# chanel.net
KiCad netlist of a schematic drawn in Altium Designer
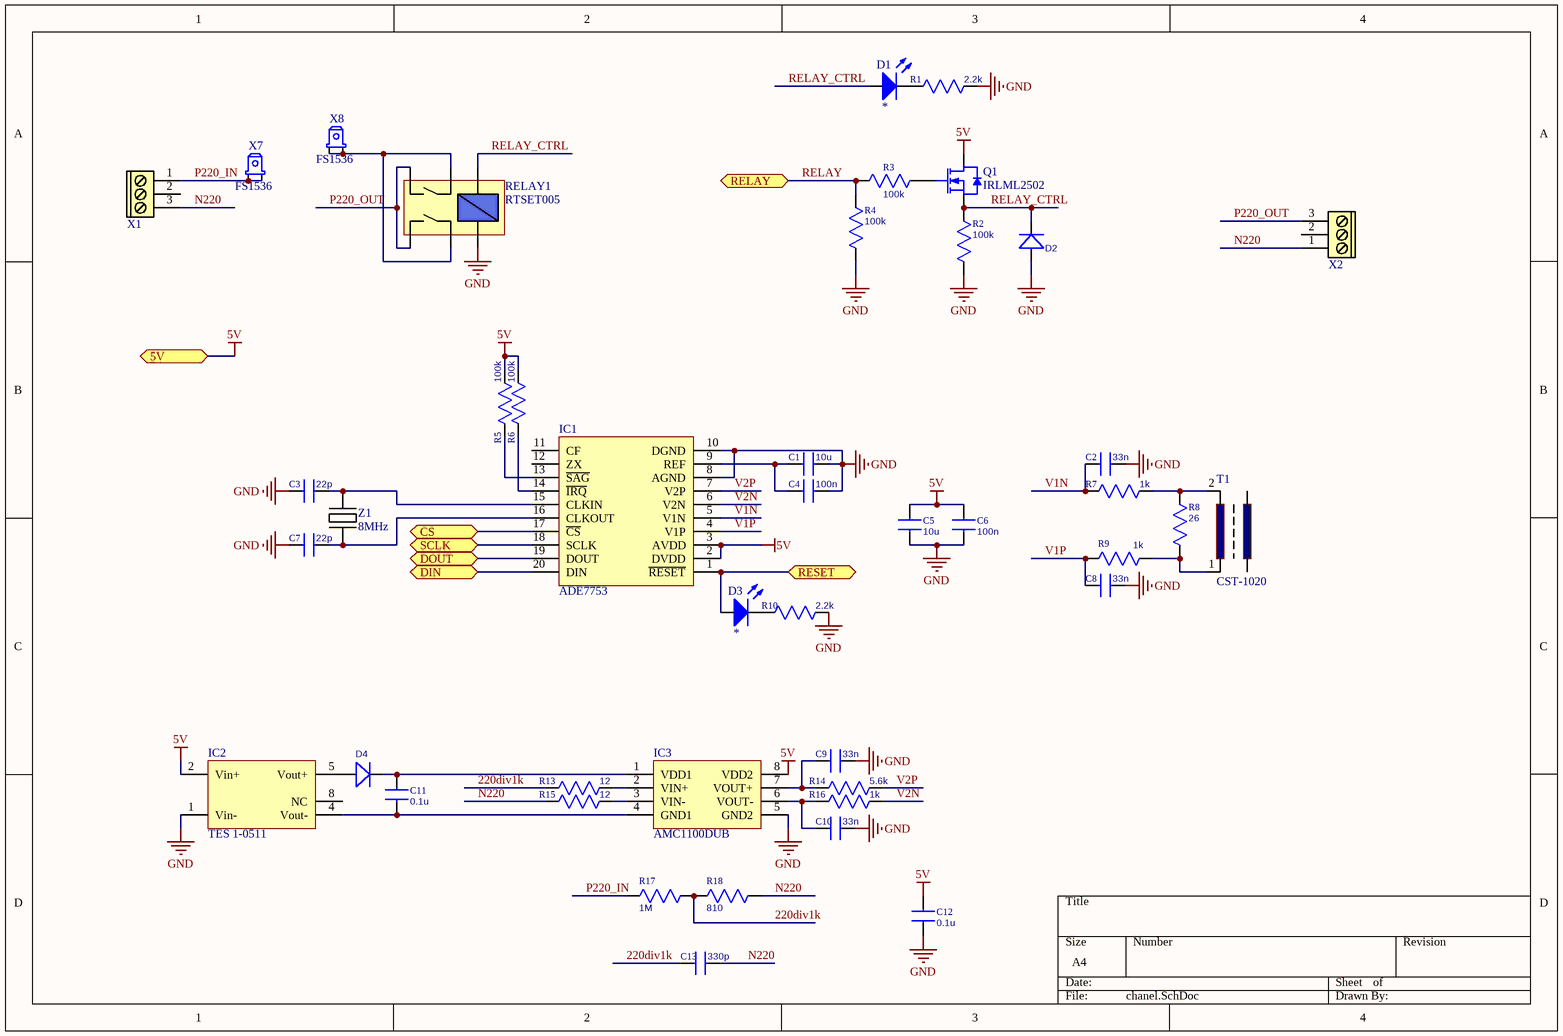
[diagram p0: chanel.SchDoc]

(export (version "E")
  (design (tool "Eeschema 10.0.6"))
  (components
    (comp (ref "C1")
      (value "10u")
      (footprint "C_0805")
      (description "Capacitor")
      (libsource (lib "AX_Altium_v2.3") (part "C0805"))
    )
    (comp (ref "C2")
      (value "33n")
      (footprint "C_0603")
      (description "Capacitor")
      (libsource (lib "AX_Altium_v2.3") (part "C0603"))
    )
    (comp (ref "C3")
      (value "22p")
      (footprint "C_0603")
      (description "Capacitor")
      (libsource (lib "AX_Altium_v2.3") (part "C0603"))
    )
    (comp (ref "C4")
      (value "100n")
      (footprint "C_0603")
      (description "Capacitor")
      (libsource (lib "AX_Altium_v2.3") (part "C0603"))
    )
    (comp (ref "C5")
      (value "10u")
      (footprint "C_0805")
      (description "Capacitor")
      (libsource (lib "AX_Altium_v2.3") (part "C0805"))
    )
    (comp (ref "C6")
      (value "100n")
      (footprint "C_0603")
      (description "Capacitor")
      (libsource (lib "AX_Altium_v2.3") (part "C0603"))
    )
    (comp (ref "C7")
      (value "22p")
      (footprint "C_0603")
      (description "Capacitor")
      (libsource (lib "AX_Altium_v2.3") (part "C0603"))
    )
    (comp (ref "C8")
      (value "33n")
      (footprint "C_0603")
      (description "Capacitor")
      (libsource (lib "AX_Altium_v2.3") (part "C0603"))
    )
    (comp (ref "C9")
      (value "33n")
      (footprint "C_0603")
      (description "Capacitor")
      (libsource (lib "AX_Altium_v2.3") (part "C0603"))
    )
    (comp (ref "C10")
      (value "33n")
      (footprint "C_0603")
      (description "Capacitor")
      (libsource (lib "AX_Altium_v2.3") (part "C0603"))
    )
    (comp (ref "C11")
      (value "0.1u")
      (footprint "C_0603")
      (description "Capacitor")
      (libsource (lib "AX_Altium_v2.3") (part "C0603"))
    )
    (comp (ref "C12")
      (value "0.1u")
      (footprint "C_0603")
      (description "Capacitor")
      (libsource (lib "AX_Altium_v2.3") (part "C0603"))
    )
    (comp (ref "C13")
      (value "330p")
      (footprint "C_0603")
      (description "Capacitor")
      (libsource (lib "AX_Altium_v2.3") (part "C0603"))
    )
    (comp (ref "D1")
      (value "*")
      (footprint "LED_5mm")
      (description "Typical INFRARED GaAs LED")
      (libsource (lib "AX_Altium_v2.3") (part "LED_5mm"))
    )
    (comp (ref "D2")
      (value "D_DO-214AC")
      (footprint "DO-214AC")
      (description "Diode")
      (libsource (lib "AX_Altium_v2.3") (part "D_DO-214AC"))
    )
    (comp (ref "D3")
      (value "*")
      (footprint "LED_5mm")
      (description "Typical INFRARED GaAs LED")
      (libsource (lib "AX_Altium_v2.3") (part "LED_5mm"))
    )
    (comp (ref "D4")
      (value "D_DO-214AC")
      (footprint "DO-214AC")
      (description "Diode")
      (libsource (lib "AX_Altium_v2.3") (part "D_DO-214AC"))
    )
    (comp (ref "IC1")
      (value "ADE7753")
      (footprint "SOP-20")
      (description "Data Acquisition ADC/DAC")
      (libsource (lib "SmartOutletIntegratedLibrary") (part "ADE7753ARSZ"))
    )
    (comp (ref "IC2")
      (value "TES 1-0511")
      (footprint "TES 1-0511")
      (description "Isolated DC/DC Converter")
      (libsource (lib "SmartOutletIntegratedLibrary") (part "TES 1-0511"))
    )
    (comp (ref "IC3")
      (value "AMC1100DUB")
      (footprint "SOP254-8N")
      (description "Isolation Amplifier 4.25kV PEAK Iso Amp")
      (libsource (lib "SmartOutletIntegratedLibrary") (part "AMC1100DUB"))
    )
    (comp (ref "Q1")
      (value "IRLML2502")
      (footprint "SOT23")
      (description "N-Channel Enhancement Mode MOSFET")
      (fields (field (name "PUBLISHER") "Altium Limited"))
      (libsource (lib "AX_Altium_v2.3") (part "N-ch_SOT23"))
    )
    (comp (ref "R1")
      (value "2.2k")
      (footprint "R_0603")
      (description "Resistor")
      (libsource (lib "AX_Altium_v2.3") (part "R0603"))
    )
    (comp (ref "R2")
      (value "100k")
      (footprint "R_0603")
      (description "Resistor")
      (libsource (lib "AX_Altium_v2.3") (part "R0603"))
    )
    (comp (ref "R3")
      (value "100k")
      (footprint "R_0603")
      (description "Resistor")
      (libsource (lib "AX_Altium_v2.3") (part "R0603"))
    )
    (comp (ref "R4")
      (value "100k")
      (footprint "R_0603")
      (description "Resistor")
      (libsource (lib "AX_Altium_v2.3") (part "R0603"))
    )
    (comp (ref "R5")
      (value "100k")
      (footprint "R_0603")
      (description "Resistor")
      (libsource (lib "AX_Altium_v2.3") (part "R0603"))
    )
    (comp (ref "R6")
      (value "100k")
      (footprint "R_0603")
      (description "Resistor")
      (libsource (lib "AX_Altium_v2.3") (part "R0603"))
    )
    (comp (ref "R7")
      (value "1k")
      (footprint "R_0603")
      (description "Resistor")
      (libsource (lib "AX_Altium_v2.3") (part "R0603"))
    )
    (comp (ref "R8")
      (value "26")
      (footprint "R_0805")
      (description "Resistor")
      (libsource (lib "AX_Altium_v2.3") (part "R0805"))
    )
    (comp (ref "R9")
      (value "1k")
      (footprint "R_0603")
      (description "Resistor")
      (libsource (lib "AX_Altium_v2.3") (part "R0603"))
    )
    (comp (ref "R10")
      (value "2.2k")
      (footprint "R_0603")
      (description "Resistor")
      (libsource (lib "AX_Altium_v2.3") (part "R0603"))
    )
    (comp (ref "R13")
      (value "12")
      (footprint "R_0603")
      (description "Resistor")
      (libsource (lib "AX_Altium_v2.3") (part "R0603"))
    )
    (comp (ref "R14")
      (value "5.6k")
      (footprint "R_0603")
      (description "Resistor")
      (libsource (lib "AX_Altium_v2.3") (part "R0603"))
    )
    (comp (ref "R15")
      (value "12")
      (footprint "R_0603")
      (description "Resistor")
      (libsource (lib "AX_Altium_v2.3") (part "R0603"))
    )
    (comp (ref "R16")
      (value "1k")
      (footprint "R_0603")
      (description "Resistor")
      (libsource (lib "AX_Altium_v2.3") (part "R0603"))
    )
    (comp (ref "R17")
      (value "1M")
      (footprint "R_0805")
      (description "Resistor")
      (libsource (lib "AX_Altium_v2.3") (part "R0805"))
    )
    (comp (ref "R18")
      (value "810")
      (footprint "R_0805")
      (description "Resistor")
      (libsource (lib "AX_Altium_v2.3") (part "R0805"))
    )
    (comp (ref "RELAY1")
      (value "RTSET005")
      (footprint "RTSET005")
      (description "General Purpose Relay")
      (libsource (lib "SmartOutletIntegratedLibrary") (part "1-1415898-8"))
    )
    (comp (ref "T1")
      (value "CST-1020")
      (footprint "CST-1020")
      (description "Current Transformer")
      (libsource (lib "SmartOutletIntegratedLibrary") (part "CST-1020"))
    )
    (comp (ref "X1")
      (value "DG-300-3")
      (footprint "DG-300-5MM-3")
      (libsource (lib "Light_Music_Integrated_Library") (part "DG-300-3"))
    )
    (comp (ref "X2") (value "DG-300-3") (footprint "DG-300-5MM-3") (libsource (lib "") (part "DG-300-3_1")))
    (comp (ref "X7")
      (value "FS1536")
      (footprint "FS1536")
      (description "PCB Soldering tips")
      (libsource (lib "SmartOutletIntegratedLibrary") (part "FS1536"))
    )
    (comp (ref "X8")
      (value "FS1536")
      (footprint "FS1536")
      (description "PCB Soldering tips")
      (libsource (lib "SmartOutletIntegratedLibrary") (part "FS1536"))
    )
    (comp (ref "Z1")
      (value "8MHz")
      (footprint "HC-49")
      (description "Quartz resonator")
      (libsource (lib "Light_Music_Integrated_Library") (part "XTAL"))
    )
  )
  (nets
    (net (code "1") (name "/220div1k") (class "Default")
      (node (ref "C13") (pin "1") (pintype "passive"))
      (node (ref "R13") (pin "1") (pintype "passive"))
      (node (ref "R17") (pin "2") (pintype "passive"))
      (node (ref "R18") (pin "1") (pintype "passive"))
    )
    (net (code "2") (name "/CS") (class "Default")
      (node (ref "IC1") (pin "17") (pinfunction "~{CS}_17") (pintype "passive"))
    )
    (net (code "3") (name "/DIN") (class "Default")
      (node (ref "IC1") (pin "20") (pinfunction "DIN_20") (pintype "passive"))
    )
    (net (code "4") (name "/DOUT") (class "Default")
      (node (ref "IC1") (pin "19") (pinfunction "DOUT_19") (pintype "passive"))
    )
    (net (code "5") (name "/N220") (class "Default")
      (node (ref "C13") (pin "2") (pintype "passive"))
      (node (ref "R15") (pin "1") (pintype "passive"))
      (node (ref "R18") (pin "2") (pintype "passive"))
      (node (ref "X1") (pin "3") (pinfunction "3_3") (pintype "passive"))
      (node (ref "X2") (pin "1") (pinfunction "1_1") (pintype "passive"))
    )
    (net (code "6") (name "/P220_IN") (class "Default")
      (node (ref "R17") (pin "1") (pintype "passive"))
      (node (ref "X1") (pin "1") (pinfunction "1_1") (pintype "passive"))
      (node (ref "X7") (pin "1") (pinfunction "1_1") (pintype "passive"))
    )
    (net (code "7") (name "/P220_OUT") (class "Default")
      (node (ref "RELAY1") (pin "1") (pinfunction "1_1") (pintype "passive"))
      (node (ref "RELAY1") (pin "2") (pinfunction "2_2") (pintype "passive"))
      (node (ref "X2") (pin "3") (pinfunction "3_3") (pintype "passive"))
    )
    (net (code "8") (name "/RELAY") (class "Default")
      (node (ref "R3") (pin "2") (pintype "passive"))
      (node (ref "R4") (pin "1") (pintype "passive"))
    )
    (net (code "9") (name "/RELAY_CTRL") (class "Default")
      (node (ref "D1") (pin "1") (pinfunction "A_1") (pintype "passive"))
      (node (ref "D2") (pin "2") (pinfunction "K_2") (pintype "passive"))
      (node (ref "Q1") (pin "2") (pinfunction "S_2") (pintype "passive"))
      (node (ref "R2") (pin "1") (pintype "passive"))
      (node (ref "RELAY1") (pin "5") (pinfunction "5_5") (pintype "passive"))
    )
    (net (code "10") (name "/RESET") (class "Default")
      (node (ref "D3") (pin "1") (pinfunction "A_1") (pintype "passive"))
      (node (ref "IC1") (pin "1") (pinfunction "~{RESET}_1") (pintype "passive"))
    )
    (net (code "11") (name "/SCLK") (class "Default")
      (node (ref "IC1") (pin "18") (pinfunction "SCLK_18") (pintype "passive"))
    )
    (net (code "12") (name "/V1N") (class "Default")
      (node (ref "C2") (pin "1") (pintype "passive"))
      (node (ref "IC1") (pin "5") (pinfunction "V1N_5") (pintype "passive"))
      (node (ref "R7") (pin "1") (pintype "passive"))
    )
    (net (code "13") (name "/V1P") (class "Default")
      (node (ref "C8") (pin "1") (pintype "passive"))
      (node (ref "IC1") (pin "4") (pinfunction "V1P_4") (pintype "passive"))
      (node (ref "R9") (pin "1") (pintype "passive"))
    )
    (net (code "14") (name "/V2N") (class "Default")
      (node (ref "IC1") (pin "6") (pinfunction "V2N_6") (pintype "passive"))
      (node (ref "R16") (pin "2") (pintype "passive"))
    )
    (net (code "15") (name "/V2P") (class "Default")
      (node (ref "IC1") (pin "7") (pinfunction "V2P_7") (pintype "passive"))
      (node (ref "R14") (pin "2") (pintype "passive"))
    )
    (net (code "16") (name "5V") (class "Default")
      (node (ref "C12") (pin "2") (pintype "passive"))
      (node (ref "C5") (pin "2") (pintype "passive"))
      (node (ref "C6") (pin "2") (pintype "passive"))
      (node (ref "IC1") (pin "2") (pinfunction "DVDD_2") (pintype "passive"))
      (node (ref "IC1") (pin "3") (pinfunction "AVDD_3") (pintype "passive"))
      (node (ref "IC2") (pin "2") (pinfunction "Vin+_2") (pintype "passive"))
      (node (ref "IC3") (pin "8") (pinfunction "VDD2_8") (pintype "passive"))
      (node (ref "Q1") (pin "3") (pinfunction "D_3") (pintype "passive"))
      (node (ref "R5") (pin "2") (pintype "passive"))
      (node (ref "R6") (pin "2") (pintype "passive"))
    )
    (net (code "17") (name "GND") (class "Default")
      (node (ref "C1") (pin "2") (pintype "passive"))
      (node (ref "C10") (pin "2") (pintype "passive"))
      (node (ref "C12") (pin "1") (pintype "passive"))
      (node (ref "C2") (pin "2") (pintype "passive"))
      (node (ref "C3") (pin "1") (pintype "passive"))
      (node (ref "C4") (pin "2") (pintype "passive"))
      (node (ref "C5") (pin "1") (pintype "passive"))
      (node (ref "C6") (pin "1") (pintype "passive"))
      (node (ref "C7") (pin "1") (pintype "passive"))
      (node (ref "C8") (pin "2") (pintype "passive"))
      (node (ref "C9") (pin "2") (pintype "passive"))
      (node (ref "D2") (pin "1") (pinfunction "A_1") (pintype "passive"))
      (node (ref "IC1") (pin "10") (pinfunction "DGND_10") (pintype "passive"))
      (node (ref "IC1") (pin "8") (pinfunction "AGND_8") (pintype "passive"))
      (node (ref "IC2") (pin "1") (pinfunction "Vin-_1") (pintype "passive"))
      (node (ref "IC3") (pin "5") (pinfunction "GND2_5") (pintype "passive"))
      (node (ref "R1") (pin "2") (pintype "passive"))
      (node (ref "R10") (pin "2") (pintype "passive"))
      (node (ref "R2") (pin "2") (pintype "passive"))
      (node (ref "R4") (pin "2") (pintype "passive"))
      (node (ref "RELAY1") (pin "6") (pinfunction "6_6") (pintype "passive"))
    )
    (net (code "18") (name "Net-(D1-K)") (class "Default")
      (node (ref "D1") (pin "2") (pinfunction "K_2") (pintype "passive"))
      (node (ref "R1") (pin "1") (pintype "passive"))
    )
    (net (code "19") (name "Net-(D3-K)") (class "Default")
      (node (ref "D3") (pin "2") (pinfunction "K_2") (pintype "passive"))
      (node (ref "R10") (pin "1") (pintype "passive"))
    )
    (net (code "20") (name "Net-(D4-A)") (class "Default")
      (node (ref "D4") (pin "1") (pinfunction "A_1") (pintype "passive"))
      (node (ref "IC2") (pin "5") (pinfunction "Vout+_5") (pintype "passive"))
    )
    (net (code "21") (name "Net-(D4-K)") (class "Default")
      (node (ref "C11") (pin "2") (pintype "passive"))
      (node (ref "D4") (pin "2") (pinfunction "K_2") (pintype "passive"))
      (node (ref "IC3") (pin "1") (pinfunction "VDD1_1") (pintype "passive"))
    )
    (net (code "22") (name "Net-(IC1-CLKIN)") (class "Default")
      (node (ref "C3") (pin "2") (pintype "passive"))
      (node (ref "IC1") (pin "15") (pinfunction "CLKIN_15") (pintype "passive"))
      (node (ref "Z1") (pin "2") (pinfunction "2_2") (pintype "passive"))
    )
    (net (code "23") (name "Net-(IC1-CLKOUT)") (class "Default")
      (node (ref "C7") (pin "2") (pintype "passive"))
      (node (ref "IC1") (pin "16") (pinfunction "CLKOUT_16") (pintype "passive"))
      (node (ref "Z1") (pin "1") (pinfunction "1_1") (pintype "passive"))
    )
    (net (code "24") (name "Net-(IC1-REF)") (class "Default")
      (node (ref "C1") (pin "1") (pintype "passive"))
      (node (ref "C4") (pin "1") (pintype "passive"))
      (node (ref "IC1") (pin "9") (pinfunction "REF_9") (pintype "passive"))
    )
    (net (code "25") (name "Net-(IC1-~{IRQ})") (class "Default")
      (node (ref "IC1") (pin "14") (pinfunction "~{IRQ}_14") (pintype "passive"))
      (node (ref "R6") (pin "1") (pintype "passive"))
    )
    (net (code "26") (name "Net-(IC1-~{SAG})") (class "Default")
      (node (ref "IC1") (pin "13") (pinfunction "~{SAG}_13") (pintype "passive"))
      (node (ref "R5") (pin "1") (pintype "passive"))
    )
    (net (code "27") (name "Net-(IC2-Vout-)") (class "Default")
      (node (ref "C11") (pin "1") (pintype "passive"))
      (node (ref "IC2") (pin "4") (pinfunction "Vout-_4") (pintype "passive"))
      (node (ref "IC3") (pin "4") (pinfunction "GND1_4") (pintype "passive"))
    )
    (net (code "28") (name "Net-(IC3-VIN+)") (class "Default")
      (node (ref "IC3") (pin "2") (pinfunction "VIN+_2") (pintype "passive"))
      (node (ref "R13") (pin "2") (pintype "passive"))
    )
    (net (code "29") (name "Net-(IC3-VIN-)") (class "Default")
      (node (ref "IC3") (pin "3") (pinfunction "VIN-_3") (pintype "passive"))
      (node (ref "R15") (pin "2") (pintype "passive"))
    )
    (net (code "30") (name "Net-(IC3-VOUT+)") (class "Default")
      (node (ref "C9") (pin "1") (pintype "passive"))
      (node (ref "IC3") (pin "7") (pinfunction "VOUT+_7") (pintype "passive"))
      (node (ref "R14") (pin "1") (pintype "passive"))
    )
    (net (code "31") (name "Net-(IC3-VOUT-)") (class "Default")
      (node (ref "C10") (pin "1") (pintype "passive"))
      (node (ref "IC3") (pin "6") (pinfunction "VOUT-_6") (pintype "passive"))
      (node (ref "R16") (pin "1") (pintype "passive"))
    )
    (net (code "32") (name "Net-(Q1-G)") (class "Default")
      (node (ref "Q1") (pin "1") (pinfunction "G_1") (pintype "passive"))
      (node (ref "R3") (pin "1") (pintype "passive"))
    )
    (net (code "33") (name "Net-(R7-Pad2)") (class "Default")
      (node (ref "R7") (pin "2") (pintype "passive"))
      (node (ref "R8") (pin "1") (pintype "passive"))
      (node (ref "T1") (pin "2") (pinfunction "2_2") (pintype "passive"))
    )
    (net (code "34") (name "Net-(R8-Pad2)") (class "Default")
      (node (ref "R8") (pin "2") (pintype "passive"))
      (node (ref "R9") (pin "2") (pintype "passive"))
      (node (ref "T1") (pin "1") (pinfunction "1_1") (pintype "passive"))
    )
    (net (code "35") (name "Net-(RELAY1-Pad3)") (class "Default")
      (node (ref "RELAY1") (pin "3") (pinfunction "3_3") (pintype "passive"))
      (node (ref "RELAY1") (pin "4") (pinfunction "4_4") (pintype "passive"))
      (node (ref "X8") (pin "1") (pinfunction "1_1") (pintype "passive"))
    )
    (net (code "36") (name "unconnected-(IC1-CF-Pad11)") (class "Default")
      (node (ref "IC1") (pin "11") (pinfunction "CF_11") (pintype "passive"))
    )
    (net (code "37") (name "unconnected-(IC1-ZX-Pad12)") (class "Default")
      (node (ref "IC1") (pin "12") (pinfunction "ZX_12") (pintype "passive"))
    )
    (net (code "38") (name "unconnected-(IC2-NC-Pad8)") (class "Default")
      (node (ref "IC2") (pin "8") (pinfunction "NC_8") (pintype "passive"))
    )
    (net (code "39") (name "unconnected-(X1-Pad2)") (class "Default")
      (node (ref "X1") (pin "2") (pinfunction "2_2") (pintype "passive"))
    )
    (net (code "40") (name "unconnected-(X2-Pad2)") (class "Default")
      (node (ref "X2") (pin "2") (pinfunction "2_2") (pintype "passive"))
    )
  )
)
